# 7seg-clock.net
KiCad netlist of a schematic drawn in EAGLE
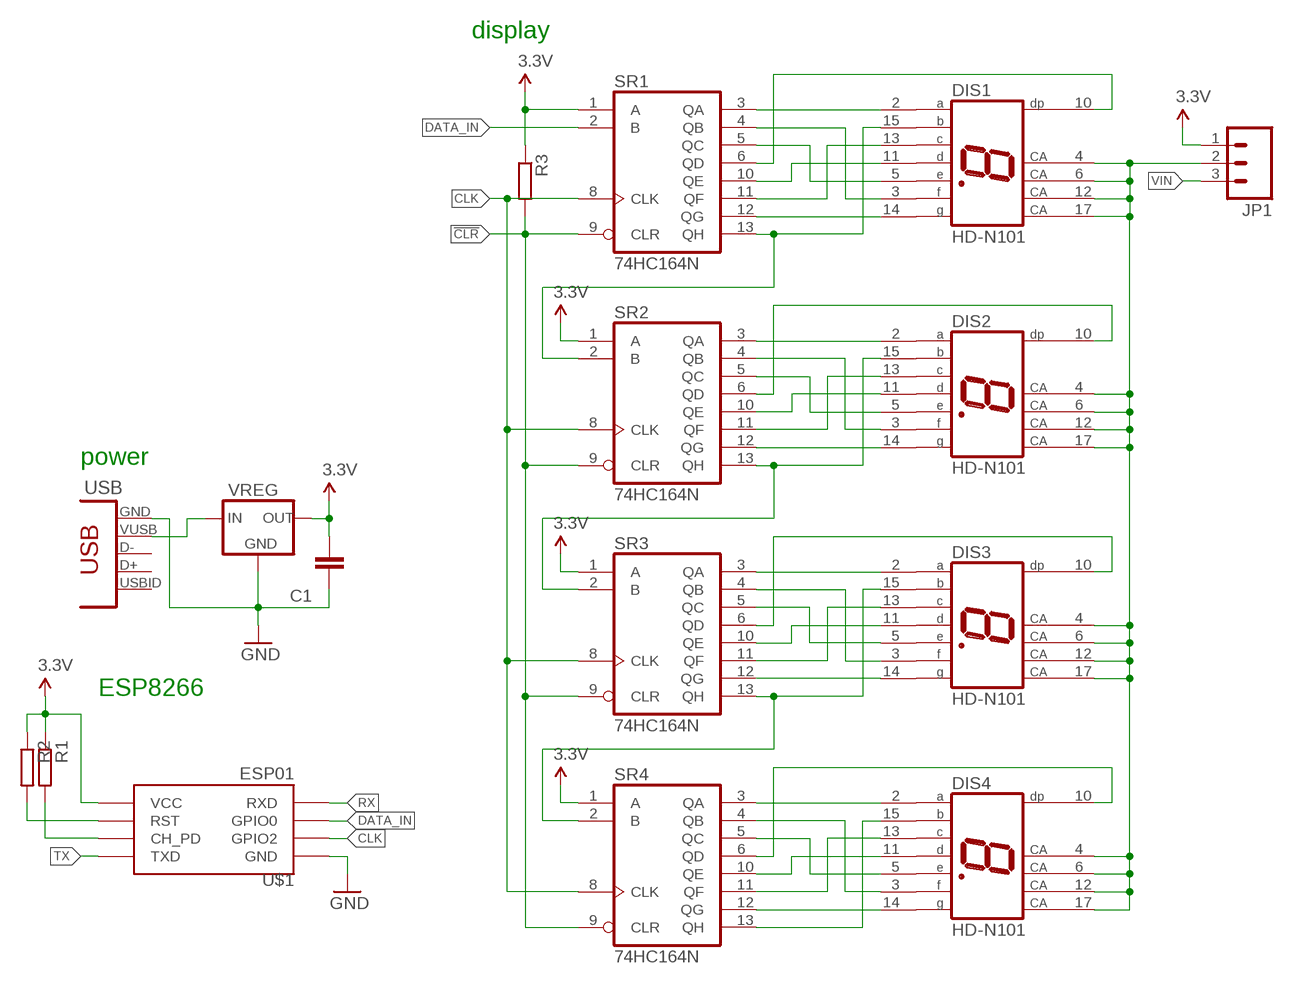
[diagram p0: schematic, sheet 1]

(export (version "E")
  (design (tool "Eeschema 10.0.6"))
  (components
    (comp (ref "C1")
      (value "CAPACITOR_NPOL-0603")
      (footprint "eagle-import:C603")
      (libsource (lib "eagle-import") (part "CAPACITOR_NPOL-0603"))
    )
    (comp (ref "DIS1")
      (value "HD-N101")
      (footprint "eagle-import:HDSP-Q")
      (libsource (lib "eagle-import") (part "HD-N101"))
    )
    (comp (ref "DIS2")
      (value "HD-N101")
      (footprint "eagle-import:HDSP-Q")
      (libsource (lib "eagle-import") (part "HD-N101"))
    )
    (comp (ref "DIS3")
      (value "HD-N101")
      (footprint "eagle-import:HDSP-Q")
      (libsource (lib "eagle-import") (part "HD-N101"))
    )
    (comp (ref "DIS4")
      (value "HD-N101")
      (footprint "eagle-import:HDSP-Q")
      (libsource (lib "eagle-import") (part "HD-N101"))
    )
    (comp (ref "JP1")
      (value "M03PTH")
      (footprint "eagle-import:1X03")
      (libsource (lib "eagle-import") (part "M03PTH"))
    )
    (comp (ref "R1")
      (value "RESISTOR-0603")
      (footprint "eagle-import:R603")
      (libsource (lib "eagle-import") (part "RESISTOR-0603"))
    )
    (comp (ref "R2")
      (value "RESISTOR-0603")
      (footprint "eagle-import:R603")
      (libsource (lib "eagle-import") (part "RESISTOR-0603"))
    )
    (comp (ref "R3")
      (value "RESISTOR-0603")
      (footprint "eagle-import:R603")
      (libsource (lib "eagle-import") (part "RESISTOR-0603"))
    )
    (comp (ref "SR1")
      (value "74HC164N")
      (footprint "eagle-import:DIL14")
      (libsource (lib "eagle-import") (part "74164NHC"))
    )
    (comp (ref "SR2")
      (value "74HC164N")
      (footprint "eagle-import:DIL14")
      (libsource (lib "eagle-import") (part "74164NHC"))
    )
    (comp (ref "SR3")
      (value "74HC164N")
      (footprint "eagle-import:DIL14")
      (libsource (lib "eagle-import") (part "74164NHC"))
    )
    (comp (ref "SR4")
      (value "74HC164N")
      (footprint "eagle-import:DIL14")
      (libsource (lib "eagle-import") (part "74164NHC"))
    )
    (comp (ref "U$1")
      (value "ESP01")
      (footprint "eagle-import:ESP01")
      (libsource (lib "eagle-import") (part "ESP01"))
    )
    (comp (ref "USB")
      (value "CON-USB-F-MICRO-B")
      (footprint "eagle-import:CONN_USB_MICRO-B")
      (libsource (lib "eagle-import") (part "CON-USB-F-MICRO-B"))
    )
    (comp (ref "VREG")
      (value "V_REG_MIC2920")
      (footprint "eagle-import:SOT223")
      (libsource (lib "eagle-import") (part "V_REG_MIC2920"))
    )
  )
  (nets
    (net (code "1") (name "/~{CLR}") (class "Default")
      (node (ref "R3") (pin "2") (pinfunction "2_2") (pintype "passive"))
      (node (ref "SR1") (pin "9") (pinfunction "CLR_9") (pintype "input"))
      (node (ref "SR2") (pin "9") (pinfunction "CLR_9") (pintype "input"))
      (node (ref "SR3") (pin "9") (pinfunction "CLR_9") (pintype "input"))
      (node (ref "SR4") (pin "9") (pinfunction "CLR_9") (pintype "input"))
    )
    (net (code "2") (name "3.3V") (class "Default")
      (node (ref "C1") (pin "2") (pinfunction "2_2") (pintype "passive"))
      (node (ref "JP1") (pin "1") (pinfunction "1_1") (pintype "passive"))
      (node (ref "R1") (pin "1") (pinfunction "1_1") (pintype "passive"))
      (node (ref "R2") (pin "1") (pinfunction "1_1") (pintype "passive"))
      (node (ref "R3") (pin "1") (pinfunction "1_1") (pintype "passive"))
      (node (ref "SR1") (pin "1") (pinfunction "A_1") (pintype "input"))
      (node (ref "SR2") (pin "1") (pinfunction "A_1") (pintype "input"))
      (node (ref "SR3") (pin "1") (pinfunction "A_1") (pintype "input"))
      (node (ref "SR4") (pin "1") (pinfunction "A_1") (pintype "input"))
      (node (ref "U$1") (pin "VCC") (pinfunction "VCC_VCC") (pintype "bidirectional"))
      (node (ref "VREG") (pin "3") (pinfunction "OUT_3") (pintype "output"))
    )
    (net (code "3") (name "CLK") (class "Default")
      (node (ref "SR1") (pin "8") (pinfunction "CLK_8") (pintype "input"))
      (node (ref "SR2") (pin "8") (pinfunction "CLK_8") (pintype "input"))
      (node (ref "SR3") (pin "8") (pinfunction "CLK_8") (pintype "input"))
      (node (ref "SR4") (pin "8") (pinfunction "CLK_8") (pintype "input"))
      (node (ref "U$1") (pin "GPIO2") (pinfunction "GPIO2_GPIO2") (pintype "bidirectional"))
    )
    (net (code "4") (name "DATA_IN") (class "Default")
      (node (ref "SR1") (pin "2") (pinfunction "B_2") (pintype "input"))
      (node (ref "U$1") (pin "GPIO0") (pinfunction "GPIO0_GPIO0") (pintype "bidirectional"))
    )
    (net (code "5") (name "GND") (class "Default")
      (node (ref "C1") (pin "1") (pinfunction "1_1") (pintype "passive"))
      (node (ref "U$1") (pin "GND") (pinfunction "GND_GND") (pintype "bidirectional"))
      (node (ref "USB") (pin "P5") (pinfunction "GND_P5") (pintype "bidirectional"))
      (node (ref "VREG") (pin "2") (pinfunction "GND_2") (pintype "input"))
      (node (ref "VREG") (pin "4") (pinfunction "GND_4") (pintype "input"))
    )
    (net (code "6") (name "Net-(DIS1-A)") (class "Default")
      (node (ref "DIS1") (pin "2") (pinfunction "A_2") (pintype "passive"))
      (node (ref "SR1") (pin "3") (pinfunction "QA_3") (pintype "output"))
    )
    (net (code "7") (name "Net-(DIS1-B)") (class "Default")
      (node (ref "DIS1") (pin "15") (pinfunction "B_15") (pintype "passive"))
      (node (ref "SR1") (pin "13") (pinfunction "QH_13") (pintype "output"))
      (node (ref "SR2") (pin "2") (pinfunction "B_2") (pintype "input"))
    )
    (net (code "8") (name "Net-(DIS1-C)") (class "Default")
      (node (ref "DIS1") (pin "13") (pinfunction "C_13") (pintype "passive"))
      (node (ref "SR1") (pin "11") (pinfunction "QF_11") (pintype "output"))
    )
    (net (code "9") (name "Net-(DIS1-CA-Pad12)") (class "Default")
      (node (ref "DIS1") (pin "12") (pinfunction "CA_12") (pintype "passive"))
      (node (ref "DIS1") (pin "17") (pinfunction "CA_17") (pintype "passive"))
      (node (ref "DIS1") (pin "4") (pinfunction "CA_4") (pintype "passive"))
      (node (ref "DIS1") (pin "6") (pinfunction "CA_6") (pintype "passive"))
      (node (ref "DIS2") (pin "12") (pinfunction "CA_12") (pintype "passive"))
      (node (ref "DIS2") (pin "17") (pinfunction "CA_17") (pintype "passive"))
      (node (ref "DIS2") (pin "4") (pinfunction "CA_4") (pintype "passive"))
      (node (ref "DIS2") (pin "6") (pinfunction "CA_6") (pintype "passive"))
      (node (ref "DIS3") (pin "12") (pinfunction "CA_12") (pintype "passive"))
      (node (ref "DIS3") (pin "17") (pinfunction "CA_17") (pintype "passive"))
      (node (ref "DIS3") (pin "4") (pinfunction "CA_4") (pintype "passive"))
      (node (ref "DIS3") (pin "6") (pinfunction "CA_6") (pintype "passive"))
      (node (ref "DIS4") (pin "12") (pinfunction "CA_12") (pintype "passive"))
      (node (ref "DIS4") (pin "17") (pinfunction "CA_17") (pintype "passive"))
      (node (ref "DIS4") (pin "4") (pinfunction "CA_4") (pintype "passive"))
      (node (ref "DIS4") (pin "6") (pinfunction "CA_6") (pintype "passive"))
      (node (ref "JP1") (pin "2") (pinfunction "2_2") (pintype "passive"))
    )
    (net (code "10") (name "Net-(DIS1-D)") (class "Default")
      (node (ref "DIS1") (pin "11") (pinfunction "D_11") (pintype "passive"))
      (node (ref "SR1") (pin "10") (pinfunction "QE_10") (pintype "output"))
    )
    (net (code "11") (name "Net-(DIS1-DP)") (class "Default")
      (node (ref "DIS1") (pin "10") (pinfunction "DP_10") (pintype "passive"))
      (node (ref "SR1") (pin "6") (pinfunction "QD_6") (pintype "output"))
    )
    (net (code "12") (name "Net-(DIS1-E)") (class "Default")
      (node (ref "DIS1") (pin "5") (pinfunction "E_5") (pintype "passive"))
      (node (ref "SR1") (pin "5") (pinfunction "QC_5") (pintype "output"))
    )
    (net (code "13") (name "Net-(DIS1-F)") (class "Default")
      (node (ref "DIS1") (pin "3") (pinfunction "F_3") (pintype "passive"))
      (node (ref "SR1") (pin "4") (pinfunction "QB_4") (pintype "output"))
    )
    (net (code "14") (name "Net-(DIS1-G)") (class "Default")
      (node (ref "DIS1") (pin "14") (pinfunction "G_14") (pintype "passive"))
      (node (ref "SR1") (pin "12") (pinfunction "QG_12") (pintype "output"))
    )
    (net (code "15") (name "Net-(DIS2-A)") (class "Default")
      (node (ref "DIS2") (pin "2") (pinfunction "A_2") (pintype "passive"))
      (node (ref "SR2") (pin "3") (pinfunction "QA_3") (pintype "output"))
    )
    (net (code "16") (name "Net-(DIS2-B)") (class "Default")
      (node (ref "DIS2") (pin "15") (pinfunction "B_15") (pintype "passive"))
      (node (ref "SR2") (pin "13") (pinfunction "QH_13") (pintype "output"))
      (node (ref "SR3") (pin "2") (pinfunction "B_2") (pintype "input"))
    )
    (net (code "17") (name "Net-(DIS2-C)") (class "Default")
      (node (ref "DIS2") (pin "13") (pinfunction "C_13") (pintype "passive"))
      (node (ref "SR2") (pin "11") (pinfunction "QF_11") (pintype "output"))
    )
    (net (code "18") (name "Net-(DIS2-D)") (class "Default")
      (node (ref "DIS2") (pin "11") (pinfunction "D_11") (pintype "passive"))
      (node (ref "SR2") (pin "10") (pinfunction "QE_10") (pintype "output"))
    )
    (net (code "19") (name "Net-(DIS2-DP)") (class "Default")
      (node (ref "DIS2") (pin "10") (pinfunction "DP_10") (pintype "passive"))
      (node (ref "SR2") (pin "6") (pinfunction "QD_6") (pintype "output"))
    )
    (net (code "20") (name "Net-(DIS2-E)") (class "Default")
      (node (ref "DIS2") (pin "5") (pinfunction "E_5") (pintype "passive"))
      (node (ref "SR2") (pin "5") (pinfunction "QC_5") (pintype "output"))
    )
    (net (code "21") (name "Net-(DIS2-F)") (class "Default")
      (node (ref "DIS2") (pin "3") (pinfunction "F_3") (pintype "passive"))
      (node (ref "SR2") (pin "4") (pinfunction "QB_4") (pintype "output"))
    )
    (net (code "22") (name "Net-(DIS2-G)") (class "Default")
      (node (ref "DIS2") (pin "14") (pinfunction "G_14") (pintype "passive"))
      (node (ref "SR2") (pin "12") (pinfunction "QG_12") (pintype "output"))
    )
    (net (code "23") (name "Net-(DIS3-A)") (class "Default")
      (node (ref "DIS3") (pin "2") (pinfunction "A_2") (pintype "passive"))
      (node (ref "SR3") (pin "3") (pinfunction "QA_3") (pintype "output"))
    )
    (net (code "24") (name "Net-(DIS3-B)") (class "Default")
      (node (ref "DIS3") (pin "15") (pinfunction "B_15") (pintype "passive"))
      (node (ref "SR3") (pin "13") (pinfunction "QH_13") (pintype "output"))
      (node (ref "SR4") (pin "2") (pinfunction "B_2") (pintype "input"))
    )
    (net (code "25") (name "Net-(DIS3-C)") (class "Default")
      (node (ref "DIS3") (pin "13") (pinfunction "C_13") (pintype "passive"))
      (node (ref "SR3") (pin "11") (pinfunction "QF_11") (pintype "output"))
    )
    (net (code "26") (name "Net-(DIS3-D)") (class "Default")
      (node (ref "DIS3") (pin "11") (pinfunction "D_11") (pintype "passive"))
      (node (ref "SR3") (pin "10") (pinfunction "QE_10") (pintype "output"))
    )
    (net (code "27") (name "Net-(DIS3-DP)") (class "Default")
      (node (ref "DIS3") (pin "10") (pinfunction "DP_10") (pintype "passive"))
      (node (ref "SR3") (pin "6") (pinfunction "QD_6") (pintype "output"))
    )
    (net (code "28") (name "Net-(DIS3-E)") (class "Default")
      (node (ref "DIS3") (pin "5") (pinfunction "E_5") (pintype "passive"))
      (node (ref "SR3") (pin "5") (pinfunction "QC_5") (pintype "output"))
    )
    (net (code "29") (name "Net-(DIS3-F)") (class "Default")
      (node (ref "DIS3") (pin "3") (pinfunction "F_3") (pintype "passive"))
      (node (ref "SR3") (pin "4") (pinfunction "QB_4") (pintype "output"))
    )
    (net (code "30") (name "Net-(DIS3-G)") (class "Default")
      (node (ref "DIS3") (pin "14") (pinfunction "G_14") (pintype "passive"))
      (node (ref "SR3") (pin "12") (pinfunction "QG_12") (pintype "output"))
    )
    (net (code "31") (name "Net-(DIS4-A)") (class "Default")
      (node (ref "DIS4") (pin "2") (pinfunction "A_2") (pintype "passive"))
      (node (ref "SR4") (pin "3") (pinfunction "QA_3") (pintype "output"))
    )
    (net (code "32") (name "Net-(DIS4-B)") (class "Default")
      (node (ref "DIS4") (pin "15") (pinfunction "B_15") (pintype "passive"))
      (node (ref "SR4") (pin "13") (pinfunction "QH_13") (pintype "output"))
    )
    (net (code "33") (name "Net-(DIS4-C)") (class "Default")
      (node (ref "DIS4") (pin "13") (pinfunction "C_13") (pintype "passive"))
      (node (ref "SR4") (pin "11") (pinfunction "QF_11") (pintype "output"))
    )
    (net (code "34") (name "Net-(DIS4-D)") (class "Default")
      (node (ref "DIS4") (pin "11") (pinfunction "D_11") (pintype "passive"))
      (node (ref "SR4") (pin "10") (pinfunction "QE_10") (pintype "output"))
    )
    (net (code "35") (name "Net-(DIS4-DP)") (class "Default")
      (node (ref "DIS4") (pin "10") (pinfunction "DP_10") (pintype "passive"))
      (node (ref "SR4") (pin "6") (pinfunction "QD_6") (pintype "output"))
    )
    (net (code "36") (name "Net-(DIS4-E)") (class "Default")
      (node (ref "DIS4") (pin "5") (pinfunction "E_5") (pintype "passive"))
      (node (ref "SR4") (pin "5") (pinfunction "QC_5") (pintype "output"))
    )
    (net (code "37") (name "Net-(DIS4-F)") (class "Default")
      (node (ref "DIS4") (pin "3") (pinfunction "F_3") (pintype "passive"))
      (node (ref "SR4") (pin "4") (pinfunction "QB_4") (pintype "output"))
    )
    (net (code "38") (name "Net-(DIS4-G)") (class "Default")
      (node (ref "DIS4") (pin "14") (pinfunction "G_14") (pintype "passive"))
      (node (ref "SR4") (pin "12") (pinfunction "QG_12") (pintype "output"))
    )
    (net (code "39") (name "Net-(R1-Pad2)") (class "Default")
      (node (ref "R1") (pin "2") (pinfunction "2_2") (pintype "passive"))
      (node (ref "U$1") (pin "CH_PD") (pinfunction "CH_PD_CH_PD") (pintype "bidirectional"))
    )
    (net (code "40") (name "Net-(R2-Pad2)") (class "Default")
      (node (ref "R2") (pin "2") (pinfunction "2_2") (pintype "passive"))
      (node (ref "U$1") (pin "RST") (pinfunction "RST_RST") (pintype "bidirectional"))
    )
    (net (code "41") (name "RX") (class "Default")
      (node (ref "U$1") (pin "RX") (pinfunction "RXD_RX") (pintype "bidirectional"))
    )
    (net (code "42") (name "TX") (class "Default")
      (node (ref "U$1") (pin "TX") (pinfunction "TXD_TX") (pintype "bidirectional"))
    )
    (net (code "43") (name "VIN") (class "Default")
      (node (ref "JP1") (pin "3") (pinfunction "3_3") (pintype "passive"))
      (node (ref "USB") (pin "P1") (pinfunction "VUSB_P1") (pintype "bidirectional"))
      (node (ref "VREG") (pin "1") (pinfunction "IN_1") (pintype "input"))
    )
    (net (code "44") (name "unconnected-(USBB-D+-PadP3)") (class "Default")
      (node (ref "USB") (pin "P3") (pinfunction "D+_P3") (pintype "bidirectional"))
    )
    (net (code "45") (name "unconnected-(USBB-D--PadP2)") (class "Default")
      (node (ref "USB") (pin "P2") (pinfunction "D-_P2") (pintype "bidirectional"))
    )
    (net (code "46") (name "unconnected-(USBB-USBID-PadP4)") (class "Default")
      (node (ref "USB") (pin "P4") (pinfunction "USBID_P4") (pintype "bidirectional"))
    )
  )
)
